# MotorController_ToniDove_SwitchingPower.net
KiCad netlist of a schematic drawn in EAGLE
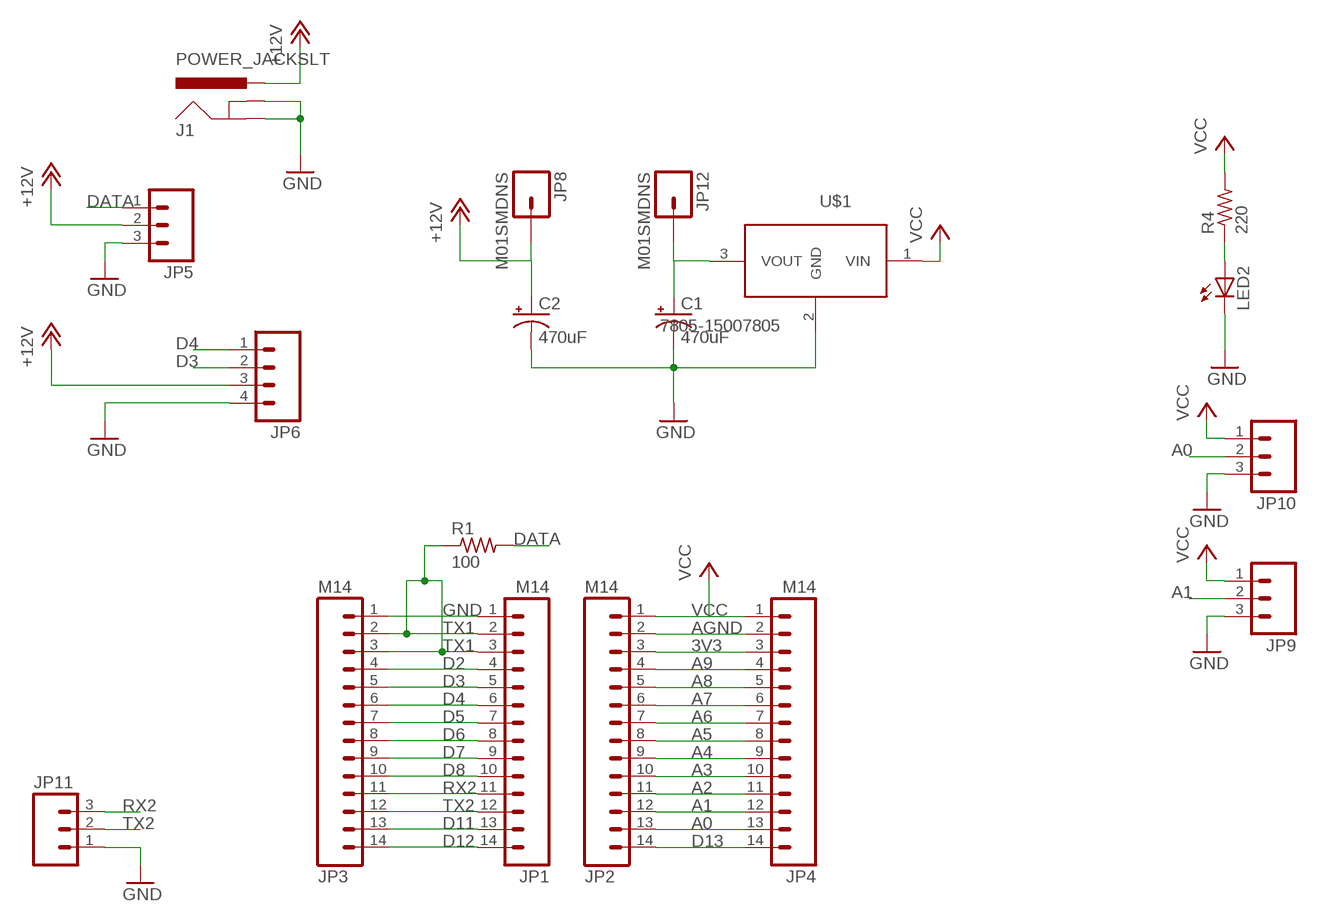
[diagram p0: schematic, sheet 1]

(export (version "E")
  (design (tool "Eeschema 10.0.6"))
  (components
    (comp (ref "C1")
      (value "470uF")
      (footprint "eagle-import:E5-13")
      (libsource (lib "eagle-import") (part "CPOL-USE5-13"))
    )
    (comp (ref "C2")
      (value "470uF")
      (footprint "eagle-import:E5-13")
      (libsource (lib "eagle-import") (part "CPOL-USE5-13"))
    )
    (comp (ref "J1")
      (value "POWER_JACKSLT")
      (footprint "eagle-import:POWER_JACK_SLOT")
      (libsource (lib "eagle-import") (part "POWER_JACKSLT"))
    )
    (comp (ref "JP1")
      (value "M14")
      (footprint "eagle-import:1X14")
      (libsource (lib "eagle-import") (part "M14"))
    )
    (comp (ref "JP2")
      (value "M14")
      (footprint "eagle-import:1X14")
      (libsource (lib "eagle-import") (part "M14"))
    )
    (comp (ref "JP3")
      (value "M14")
      (footprint "eagle-import:1X14")
      (libsource (lib "eagle-import") (part "M14"))
    )
    (comp (ref "JP4")
      (value "M14")
      (footprint "eagle-import:1X14")
      (libsource (lib "eagle-import") (part "M14"))
    )
    (comp (ref "JP5")
      (value "M03PTH")
      (footprint "eagle-import:1X03")
      (libsource (lib "eagle-import") (part "M03PTH"))
    )
    (comp (ref "JP6")
      (value "M04PTH")
      (footprint "eagle-import:1X04")
      (libsource (lib "eagle-import") (part "M04PTH"))
    )
    (comp (ref "JP8")
      (value "M01SMDNS")
      (footprint "eagle-import:1X01NS")
      (libsource (lib "eagle-import") (part "M01SMDNS"))
    )
    (comp (ref "JP9")
      (value "M03PTH")
      (footprint "eagle-import:1X03")
      (libsource (lib "eagle-import") (part "M03PTH"))
    )
    (comp (ref "JP10")
      (value "M03PTH")
      (footprint "eagle-import:1X03")
      (libsource (lib "eagle-import") (part "M03PTH"))
    )
    (comp (ref "JP11")
      (value "M03PTH")
      (footprint "eagle-import:1X03")
      (libsource (lib "eagle-import") (part "M03PTH"))
    )
    (comp (ref "JP12")
      (value "M01SMDNS")
      (footprint "eagle-import:1X01NS")
      (libsource (lib "eagle-import") (part "M01SMDNS"))
    )
    (comp (ref "LED2")
      (value "LED5MM")
      (footprint "eagle-import:LED5MM")
      (libsource (lib "eagle-import") (part "LED5MM"))
    )
    (comp (ref "R1")
      (value "100")
      (footprint "eagle-import:0204_7")
      (libsource (lib "eagle-import") (part "R-US_0204/7"))
    )
    (comp (ref "R4")
      (value "220")
      (footprint "eagle-import:0204_7")
      (libsource (lib "eagle-import") (part "R-US_0204/7"))
    )
    (comp (ref "U$1")
      (value "7805-15007805")
      (footprint "eagle-import:UL94-V0")
      (libsource (lib "eagle-import") (part "7805-15007805"))
    )
  )
  (nets
    (net (code "1") (name "+12V") (class "Default")
      (node (ref "C2") (pin "+") (pinfunction "+_+") (pintype "passive"))
      (node (ref "J1") (pin "PWR") (pinfunction "PWR_PWR") (pintype "bidirectional"))
      (node (ref "JP5") (pin "2") (pinfunction "2_2") (pintype "passive"))
      (node (ref "JP6") (pin "3") (pinfunction "3_3") (pintype "passive"))
      (node (ref "JP8") (pin "1") (pinfunction "1_1") (pintype "passive"))
    )
    (net (code "2") (name "/3V3") (class "Default")
      (node (ref "JP2") (pin "3") (pinfunction "3_3") (pintype "passive"))
      (node (ref "JP4") (pin "3") (pinfunction "3_3") (pintype "passive"))
    )
    (net (code "3") (name "/A0") (class "Default")
      (node (ref "JP10") (pin "2") (pinfunction "2_2") (pintype "passive"))
      (node (ref "JP2") (pin "13") (pinfunction "13_13") (pintype "passive"))
      (node (ref "JP4") (pin "13") (pinfunction "13_13") (pintype "passive"))
    )
    (net (code "4") (name "/A1") (class "Default")
      (node (ref "JP2") (pin "12") (pinfunction "12_12") (pintype "passive"))
      (node (ref "JP4") (pin "12") (pinfunction "12_12") (pintype "passive"))
      (node (ref "JP9") (pin "2") (pinfunction "2_2") (pintype "passive"))
    )
    (net (code "5") (name "/A2") (class "Default")
      (node (ref "JP2") (pin "11") (pinfunction "11_11") (pintype "passive"))
      (node (ref "JP4") (pin "11") (pinfunction "11_11") (pintype "passive"))
    )
    (net (code "6") (name "/A3") (class "Default")
      (node (ref "JP2") (pin "10") (pinfunction "10_10") (pintype "passive"))
      (node (ref "JP4") (pin "10") (pinfunction "10_10") (pintype "passive"))
    )
    (net (code "7") (name "/A4") (class "Default")
      (node (ref "JP2") (pin "9") (pinfunction "9_9") (pintype "passive"))
      (node (ref "JP4") (pin "9") (pinfunction "9_9") (pintype "passive"))
    )
    (net (code "8") (name "/A5") (class "Default")
      (node (ref "JP2") (pin "8") (pinfunction "8_8") (pintype "passive"))
      (node (ref "JP4") (pin "8") (pinfunction "8_8") (pintype "passive"))
    )
    (net (code "9") (name "/A6") (class "Default")
      (node (ref "JP2") (pin "7") (pinfunction "7_7") (pintype "passive"))
      (node (ref "JP4") (pin "7") (pinfunction "7_7") (pintype "passive"))
    )
    (net (code "10") (name "/A7") (class "Default")
      (node (ref "JP2") (pin "6") (pinfunction "6_6") (pintype "passive"))
      (node (ref "JP4") (pin "6") (pinfunction "6_6") (pintype "passive"))
    )
    (net (code "11") (name "/A8") (class "Default")
      (node (ref "JP2") (pin "5") (pinfunction "5_5") (pintype "passive"))
      (node (ref "JP4") (pin "5") (pinfunction "5_5") (pintype "passive"))
    )
    (net (code "12") (name "/A9") (class "Default")
      (node (ref "JP2") (pin "4") (pinfunction "4_4") (pintype "passive"))
      (node (ref "JP4") (pin "4") (pinfunction "4_4") (pintype "passive"))
    )
    (net (code "13") (name "/AGND") (class "Default")
      (node (ref "JP2") (pin "2") (pinfunction "2_2") (pintype "passive"))
      (node (ref "JP4") (pin "2") (pinfunction "2_2") (pintype "passive"))
    )
    (net (code "14") (name "/D2") (class "Default")
      (node (ref "JP1") (pin "4") (pinfunction "4_4") (pintype "passive"))
      (node (ref "JP3") (pin "4") (pinfunction "4_4") (pintype "passive"))
    )
    (net (code "15") (name "/D3") (class "Default")
      (node (ref "JP1") (pin "5") (pinfunction "5_5") (pintype "passive"))
      (node (ref "JP3") (pin "5") (pinfunction "5_5") (pintype "passive"))
      (node (ref "JP6") (pin "2") (pinfunction "2_2") (pintype "passive"))
    )
    (net (code "16") (name "/D4") (class "Default")
      (node (ref "JP1") (pin "6") (pinfunction "6_6") (pintype "passive"))
      (node (ref "JP3") (pin "6") (pinfunction "6_6") (pintype "passive"))
      (node (ref "JP6") (pin "1") (pinfunction "1_1") (pintype "passive"))
    )
    (net (code "17") (name "/D5") (class "Default")
      (node (ref "JP1") (pin "7") (pinfunction "7_7") (pintype "passive"))
      (node (ref "JP3") (pin "7") (pinfunction "7_7") (pintype "passive"))
    )
    (net (code "18") (name "/D6") (class "Default")
      (node (ref "JP1") (pin "8") (pinfunction "8_8") (pintype "passive"))
      (node (ref "JP3") (pin "8") (pinfunction "8_8") (pintype "passive"))
    )
    (net (code "19") (name "/D7") (class "Default")
      (node (ref "JP1") (pin "9") (pinfunction "9_9") (pintype "passive"))
      (node (ref "JP3") (pin "9") (pinfunction "9_9") (pintype "passive"))
    )
    (net (code "20") (name "/D8") (class "Default")
      (node (ref "JP1") (pin "10") (pinfunction "10_10") (pintype "passive"))
      (node (ref "JP3") (pin "10") (pinfunction "10_10") (pintype "passive"))
    )
    (net (code "21") (name "/D11") (class "Default")
      (node (ref "JP1") (pin "13") (pinfunction "13_13") (pintype "passive"))
      (node (ref "JP3") (pin "13") (pinfunction "13_13") (pintype "passive"))
    )
    (net (code "22") (name "/D12") (class "Default")
      (node (ref "JP1") (pin "14") (pinfunction "14_14") (pintype "passive"))
      (node (ref "JP3") (pin "14") (pinfunction "14_14") (pintype "passive"))
    )
    (net (code "23") (name "/D13") (class "Default")
      (node (ref "JP2") (pin "14") (pinfunction "14_14") (pintype "passive"))
      (node (ref "JP4") (pin "14") (pinfunction "14_14") (pintype "passive"))
    )
    (net (code "24") (name "/DATA") (class "Default")
      (node (ref "JP5") (pin "1") (pinfunction "1_1") (pintype "passive"))
      (node (ref "R1") (pin "2") (pinfunction "2_2") (pintype "passive"))
    )
    (net (code "25") (name "/RX2") (class "Default")
      (node (ref "JP1") (pin "11") (pinfunction "11_11") (pintype "passive"))
      (node (ref "JP11") (pin "3") (pinfunction "3_3") (pintype "passive"))
      (node (ref "JP3") (pin "11") (pinfunction "11_11") (pintype "passive"))
    )
    (net (code "26") (name "/TX1") (class "Default")
      (node (ref "JP1") (pin "2") (pinfunction "2_2") (pintype "passive"))
      (node (ref "JP1") (pin "3") (pinfunction "3_3") (pintype "passive"))
      (node (ref "JP3") (pin "2") (pinfunction "2_2") (pintype "passive"))
      (node (ref "JP3") (pin "3") (pinfunction "3_3") (pintype "passive"))
      (node (ref "R1") (pin "1") (pinfunction "1_1") (pintype "passive"))
    )
    (net (code "27") (name "/TX2") (class "Default")
      (node (ref "JP1") (pin "12") (pinfunction "12_12") (pintype "passive"))
      (node (ref "JP11") (pin "2") (pinfunction "2_2") (pintype "passive"))
      (node (ref "JP3") (pin "12") (pinfunction "12_12") (pintype "passive"))
    )
    (net (code "28") (name "GND") (class "Default")
      (node (ref "C1") (pin "-") (pinfunction "-_-") (pintype "passive"))
      (node (ref "C2") (pin "-") (pinfunction "-_-") (pintype "passive"))
      (node (ref "J1") (pin "GND@1") (pinfunction "GNDBREAK_GND@1") (pintype "bidirectional"))
      (node (ref "J1") (pin "GND@2") (pinfunction "GND_GND@2") (pintype "bidirectional"))
      (node (ref "JP1") (pin "1") (pinfunction "1_1") (pintype "passive"))
      (node (ref "JP10") (pin "3") (pinfunction "3_3") (pintype "passive"))
      (node (ref "JP11") (pin "1") (pinfunction "1_1") (pintype "passive"))
      (node (ref "JP3") (pin "1") (pinfunction "1_1") (pintype "passive"))
      (node (ref "JP5") (pin "3") (pinfunction "3_3") (pintype "passive"))
      (node (ref "JP6") (pin "4") (pinfunction "4_4") (pintype "passive"))
      (node (ref "JP9") (pin "3") (pinfunction "3_3") (pintype "passive"))
      (node (ref "LED2") (pin "K") (pinfunction "C_K") (pintype "passive"))
      (node (ref "U$1") (pin "2") (pinfunction "GND_2") (pintype "bidirectional"))
    )
    (net (code "29") (name "Net-(LED2-PadA)") (class "Default")
      (node (ref "LED2") (pin "A") (pinfunction "A_A") (pintype "passive"))
      (node (ref "R4") (pin "1") (pinfunction "1_1") (pintype "passive"))
    )
    (net (code "30") (name "Net-(U$1-VOUT)") (class "Default")
      (node (ref "C1") (pin "+") (pinfunction "+_+") (pintype "passive"))
      (node (ref "JP12") (pin "1") (pinfunction "1_1") (pintype "passive"))
      (node (ref "U$1") (pin "3") (pinfunction "VOUT_3") (pintype "bidirectional"))
    )
    (net (code "31") (name "VCC") (class "Default")
      (node (ref "JP10") (pin "1") (pinfunction "1_1") (pintype "passive"))
      (node (ref "JP2") (pin "1") (pinfunction "1_1") (pintype "passive"))
      (node (ref "JP4") (pin "1") (pinfunction "1_1") (pintype "passive"))
      (node (ref "JP9") (pin "1") (pinfunction "1_1") (pintype "passive"))
      (node (ref "R4") (pin "2") (pinfunction "2_2") (pintype "passive"))
      (node (ref "U$1") (pin "1") (pinfunction "VIN_1") (pintype "bidirectional"))
    )
  )
)
